# PCB_Plates_Combined_Eagle.net
KiCad netlist of a schematic drawn in EAGLE
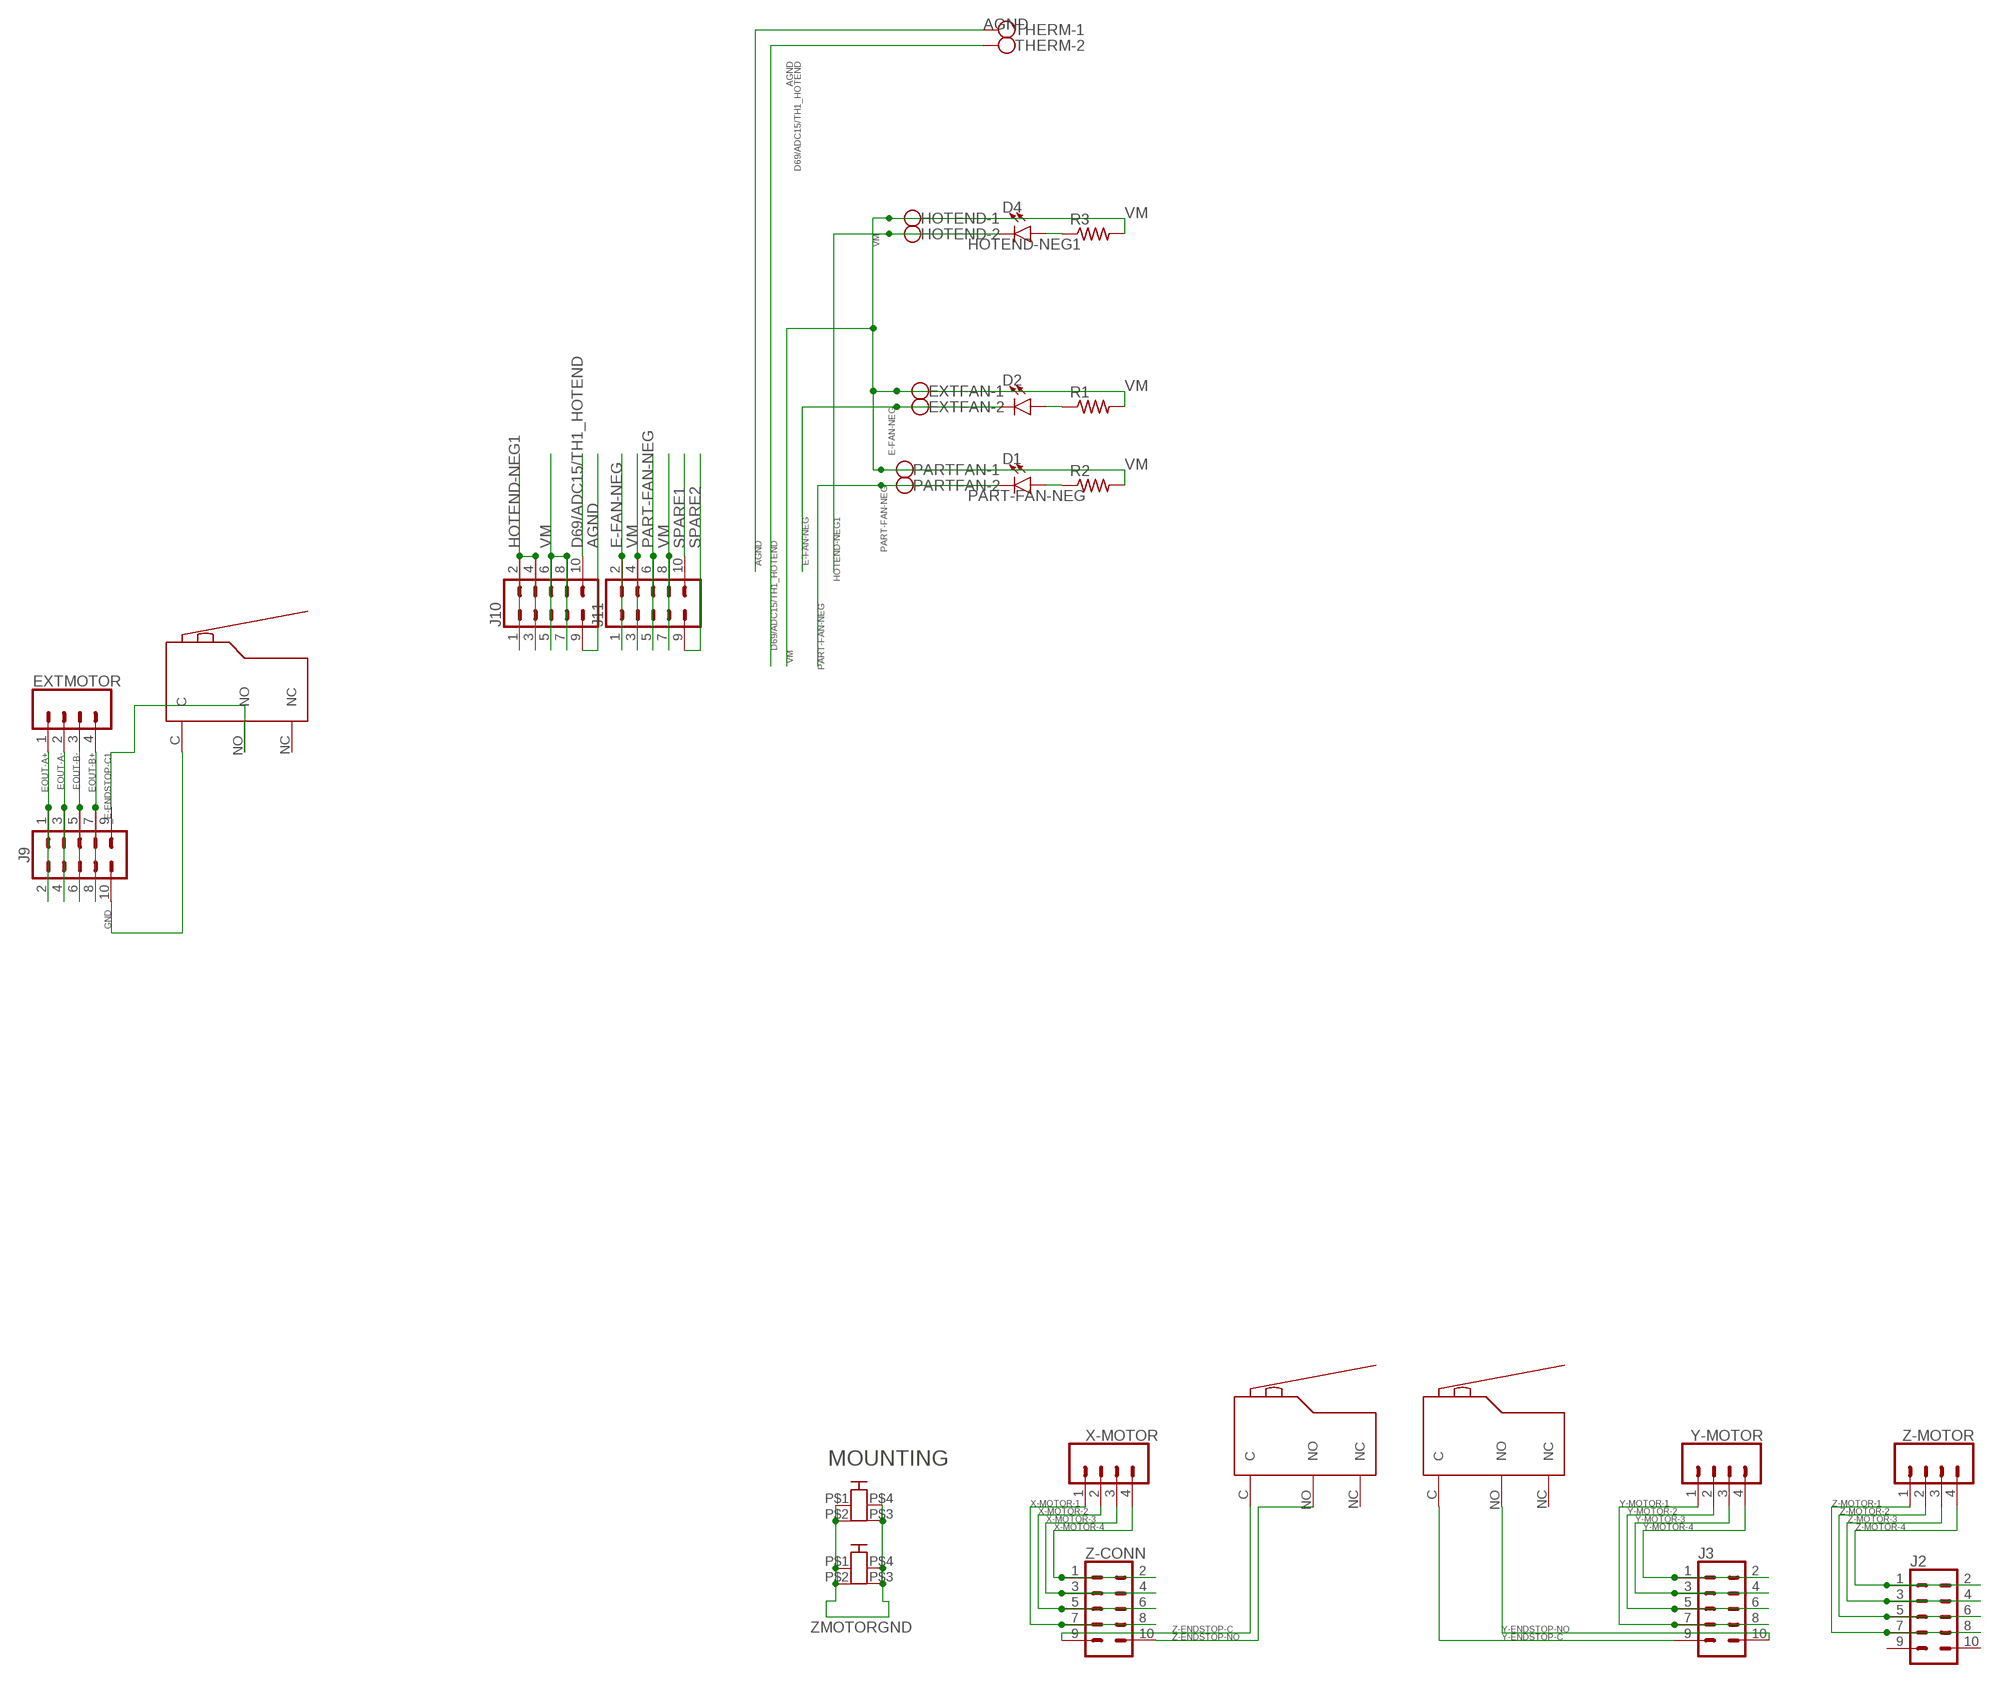
[diagram p0: schematic, sheet 1]

(export (version "E")
  (design (tool "Eeschema 10.0.6"))
  (components
    (comp (ref "CON1")
      (value "PCB-2M3")
      (footprint "eagle-import:PCB2-M3")
      (libsource (lib "eagle-import") (part "PCB-2M3"))
    )
    (comp (ref "CON7")
      (value "PCB-2M3")
      (footprint "eagle-import:PCB2-M3")
      (libsource (lib "eagle-import") (part "PCB-2M3"))
    )
    (comp (ref "D1")
      (value "LED-FKIT-1206")
      (footprint "eagle-import:FKIT-LED-1206")
      (libsource (lib "eagle-import") (part "LED-FKIT-1206"))
    )
    (comp (ref "D2")
      (value "LED-FKIT-1206")
      (footprint "eagle-import:FKIT-LED-1206")
      (libsource (lib "eagle-import") (part "LED-FKIT-1206"))
    )
    (comp (ref "D4")
      (value "LED-FKIT-1206")
      (footprint "eagle-import:FKIT-LED-1206")
      (libsource (lib "eagle-import") (part "LED-FKIT-1206"))
    )
    (comp (ref "EXTFAN")
      (value "W237-102")
      (footprint "eagle-import:W237-102")
      (fields (field (name "MPN") "237-102"))
      (libsource (lib "eagle-import") (part "W237-102"))
    )
    (comp (ref "EXTMOTOR")
      (value "CONN_04SCREW_LOCK")
      (footprint "eagle-import:SCREWTERMINAL-3.5MM-4_LOCK")
      (libsource (lib "eagle-import") (part "CONN_04SCREW_LOCK"))
    )
    (comp (ref "HOTEND")
      (value "W237-102")
      (footprint "eagle-import:W237-102")
      (fields (field (name "MPN") "237-102"))
      (libsource (lib "eagle-import") (part "W237-102"))
    )
    (comp (ref "J2")
      (value "CONN_05X2SHD_LOCK")
      (footprint "eagle-import:2X5-SHROUDED_LOCK")
      (libsource (lib "eagle-import") (part "CONN_05X2SHD_LOCK"))
    )
    (comp (ref "J3")
      (value "CONN_05X2SHD_LOCK")
      (footprint "eagle-import:2X5-SHROUDED_LOCK")
      (libsource (lib "eagle-import") (part "CONN_05X2SHD_LOCK"))
    )
    (comp (ref "J9")
      (value "CONN_05X2SHD_LOCK")
      (footprint "eagle-import:2X5-SHROUDED_LOCK")
      (libsource (lib "eagle-import") (part "CONN_05X2SHD_LOCK"))
    )
    (comp (ref "J10")
      (value "CONN_05X2SHD_LOCK")
      (footprint "eagle-import:2X5-SHROUDED_LOCK")
      (libsource (lib "eagle-import") (part "CONN_05X2SHD_LOCK"))
    )
    (comp (ref "J11")
      (value "CONN_05X2SHD_LOCK")
      (footprint "eagle-import:2X5-SHROUDED_LOCK")
      (libsource (lib "eagle-import") (part "CONN_05X2SHD_LOCK"))
    )
    (comp (ref "PARTFAN")
      (value "W237-102")
      (footprint "eagle-import:W237-102")
      (fields (field (name "MPN") "237-102"))
      (libsource (lib "eagle-import") (part "W237-102"))
    )
    (comp (ref "R1")
      (value "R-US_R1206")
      (footprint "eagle-import:R1206")
      (libsource (lib "eagle-import") (part "R-US_R1206"))
    )
    (comp (ref "R2")
      (value "R-US_R1206")
      (footprint "eagle-import:R1206")
      (libsource (lib "eagle-import") (part "R-US_R1206"))
    )
    (comp (ref "R3")
      (value "R-US_R1206")
      (footprint "eagle-import:R1206")
      (libsource (lib "eagle-import") (part "R-US_R1206"))
    )
    (comp (ref "THERM")
      (value "W237-102")
      (footprint "eagle-import:W237-102")
      (fields (field (name "MPN") "237-102"))
      (libsource (lib "eagle-import") (part "W237-102"))
    )
    (comp (ref "U$1")
      (value "Lever Microswitch Leftangle PCB mount, with Roller style lever, with a red roller")
      (footprint "eagle-import:LEVERMICROPCB-LEFTANGLE")
      (libsource (lib "eagle-import") (part "LEVERMICROPCBLEFTANGLE"))
    )
    (comp (ref "X-MOTOR")
      (value "CONN_04SCREW_LOCK")
      (footprint "eagle-import:SCREWTERMINAL-3.5MM-4_LOCK")
      (libsource (lib "eagle-import") (part "CONN_04SCREW_LOCK"))
    )
    (comp (ref "XENDSTOP")
      (value "Lever Microswitch Leftangle PCB mount, with Roller style lever, with a red roller")
      (footprint "eagle-import:LEVERMICROPCB-LEFTANGLE")
      (libsource (lib "eagle-import") (part "LEVERMICROPCBLEFTANGLE"))
    )
    (comp (ref "Y-MOTOR")
      (value "CONN_04SCREW_LOCK")
      (footprint "eagle-import:SCREWTERMINAL-3.5MM-4_LOCK")
      (libsource (lib "eagle-import") (part "CONN_04SCREW_LOCK"))
    )
    (comp (ref "Z-CONN")
      (value "CONN_05X2SHD_LOCK")
      (footprint "eagle-import:2X5-SHROUDED_LOCK")
      (libsource (lib "eagle-import") (part "CONN_05X2SHD_LOCK"))
    )
    (comp (ref "Z-MOTOR")
      (value "CONN_04SCREW_LOCK")
      (footprint "eagle-import:SCREWTERMINAL-3.5MM-4_LOCK")
      (libsource (lib "eagle-import") (part "CONN_04SCREW_LOCK"))
    )
    (comp (ref "ZENDSTOP")
      (value "Lever Microswitch Leftangle PCB mount, with Roller style lever, with a red roller")
      (footprint "eagle-import:LEVERMICROPCB-LEFTANGLE")
      (libsource (lib "eagle-import") (part "LEVERMICROPCBLEFTANGLE"))
    )
  )
  (nets
    (net (code "1") (name "/AGND") (class "Default")
      (node (ref "J10") (pin "9") (pinfunction "9_9") (pintype "passive"))
      (node (ref "THERM") (pin "1") (pinfunction "KL_1") (pintype "passive"))
    )
    (net (code "2") (name "/D69{slash}ADC15{slash}TH1_HOTEND") (class "Default")
      (node (ref "J10") (pin "10") (pinfunction "10_10") (pintype "passive"))
      (node (ref "THERM") (pin "2") (pinfunction "KL_2") (pintype "passive"))
    )
    (net (code "3") (name "/E-FAN-NEG") (class "Default")
      (node (ref "D2") (pin "C") (pinfunction "C_C") (pintype "passive"))
      (node (ref "EXTFAN") (pin "2") (pinfunction "KL_2") (pintype "passive"))
      (node (ref "J11") (pin "1") (pinfunction "1_1") (pintype "passive"))
      (node (ref "J11") (pin "2") (pinfunction "2_2") (pintype "passive"))
    )
    (net (code "4") (name "/EOUT-A+") (class "Default")
      (node (ref "EXTMOTOR") (pin "1") (pinfunction "1_1") (pintype "passive"))
      (node (ref "J9") (pin "1") (pinfunction "1_1") (pintype "passive"))
      (node (ref "J9") (pin "2") (pinfunction "2_2") (pintype "passive"))
    )
    (net (code "5") (name "/EOUT-A-") (class "Default")
      (node (ref "EXTMOTOR") (pin "2") (pinfunction "2_2") (pintype "passive"))
      (node (ref "J9") (pin "3") (pinfunction "3_3") (pintype "passive"))
      (node (ref "J9") (pin "4") (pinfunction "4_4") (pintype "passive"))
    )
    (net (code "6") (name "/EOUT-B+") (class "Default")
      (node (ref "EXTMOTOR") (pin "4") (pinfunction "4_4") (pintype "passive"))
      (node (ref "J9") (pin "7") (pinfunction "7_7") (pintype "passive"))
      (node (ref "J9") (pin "8") (pinfunction "8_8") (pintype "passive"))
    )
    (net (code "7") (name "/EOUT-B-") (class "Default")
      (node (ref "EXTMOTOR") (pin "3") (pinfunction "3_3") (pintype "passive"))
      (node (ref "J9") (pin "5") (pinfunction "5_5") (pintype "passive"))
      (node (ref "J9") (pin "6") (pinfunction "6_6") (pintype "passive"))
    )
    (net (code "8") (name "/GND") (class "Default")
      (node (ref "J9") (pin "10") (pinfunction "10_10") (pintype "passive"))
      (node (ref "XENDSTOP") (pin "C") (pinfunction "C_C") (pintype "bidirectional"))
    )
    (net (code "9") (name "/HOTEND-NEG1") (class "Default")
      (node (ref "D4") (pin "C") (pinfunction "C_C") (pintype "passive"))
      (node (ref "HOTEND") (pin "2") (pinfunction "KL_2") (pintype "passive"))
      (node (ref "J10") (pin "1") (pinfunction "1_1") (pintype "passive"))
      (node (ref "J10") (pin "2") (pinfunction "2_2") (pintype "passive"))
      (node (ref "J10") (pin "3") (pinfunction "3_3") (pintype "passive"))
      (node (ref "J10") (pin "4") (pinfunction "4_4") (pintype "passive"))
    )
    (net (code "10") (name "/PART-FAN-NEG") (class "Default")
      (node (ref "D1") (pin "C") (pinfunction "C_C") (pintype "passive"))
      (node (ref "J11") (pin "5") (pinfunction "5_5") (pintype "passive"))
      (node (ref "J11") (pin "6") (pinfunction "6_6") (pintype "passive"))
      (node (ref "PARTFAN") (pin "2") (pinfunction "KL_2") (pintype "passive"))
    )
    (net (code "11") (name "/SPARE1") (class "Default")
      (node (ref "J11") (pin "10") (pinfunction "10_10") (pintype "passive"))
    )
    (net (code "12") (name "/SPARE2") (class "Default")
      (node (ref "J11") (pin "9") (pinfunction "9_9") (pintype "passive"))
    )
    (net (code "13") (name "/VM") (class "Default")
      (node (ref "EXTFAN") (pin "1") (pinfunction "KL_1") (pintype "passive"))
      (node (ref "HOTEND") (pin "1") (pinfunction "KL_1") (pintype "passive"))
      (node (ref "J10") (pin "5") (pinfunction "5_5") (pintype "passive"))
      (node (ref "J10") (pin "6") (pinfunction "6_6") (pintype "passive"))
      (node (ref "J10") (pin "7") (pinfunction "7_7") (pintype "passive"))
      (node (ref "J10") (pin "8") (pinfunction "8_8") (pintype "passive"))
      (node (ref "J11") (pin "3") (pinfunction "3_3") (pintype "passive"))
      (node (ref "J11") (pin "4") (pinfunction "4_4") (pintype "passive"))
      (node (ref "J11") (pin "7") (pinfunction "7_7") (pintype "passive"))
      (node (ref "J11") (pin "8") (pinfunction "8_8") (pintype "passive"))
      (node (ref "PARTFAN") (pin "1") (pinfunction "KL_1") (pintype "passive"))
      (node (ref "R1") (pin "2") (pinfunction "2_2") (pintype "passive"))
      (node (ref "R2") (pin "2") (pinfunction "2_2") (pintype "passive"))
      (node (ref "R3") (pin "2") (pinfunction "2_2") (pintype "passive"))
    )
    (net (code "14") (name "/X-MOTOR-1") (class "Default")
      (node (ref "X-MOTOR") (pin "1") (pinfunction "1_1") (pintype "passive"))
      (node (ref "Z-CONN") (pin "7") (pinfunction "7_7") (pintype "passive"))
      (node (ref "Z-CONN") (pin "8") (pinfunction "8_8") (pintype "passive"))
    )
    (net (code "15") (name "/X-MOTOR-2") (class "Default")
      (node (ref "X-MOTOR") (pin "2") (pinfunction "2_2") (pintype "passive"))
      (node (ref "Z-CONN") (pin "5") (pinfunction "5_5") (pintype "passive"))
      (node (ref "Z-CONN") (pin "6") (pinfunction "6_6") (pintype "passive"))
    )
    (net (code "16") (name "/X-MOTOR-3") (class "Default")
      (node (ref "X-MOTOR") (pin "3") (pinfunction "3_3") (pintype "passive"))
      (node (ref "Z-CONN") (pin "3") (pinfunction "3_3") (pintype "passive"))
      (node (ref "Z-CONN") (pin "4") (pinfunction "4_4") (pintype "passive"))
    )
    (net (code "17") (name "/X-MOTOR-4") (class "Default")
      (node (ref "X-MOTOR") (pin "4") (pinfunction "4_4") (pintype "passive"))
      (node (ref "Z-CONN") (pin "1") (pinfunction "1_1") (pintype "passive"))
      (node (ref "Z-CONN") (pin "2") (pinfunction "2_2") (pintype "passive"))
    )
    (net (code "18") (name "/Y-ENDSTOP-C") (class "Default")
      (node (ref "J3") (pin "9") (pinfunction "9_9") (pintype "passive"))
      (node (ref "U$1") (pin "C") (pinfunction "C_C") (pintype "bidirectional"))
    )
    (net (code "19") (name "/Y-ENDSTOP-NO") (class "Default")
      (node (ref "J3") (pin "10") (pinfunction "10_10") (pintype "passive"))
      (node (ref "U$1") (pin "NO") (pinfunction "NO_NO") (pintype "bidirectional"))
    )
    (net (code "20") (name "/Y-MOTOR-1") (class "Default")
      (node (ref "J3") (pin "7") (pinfunction "7_7") (pintype "passive"))
      (node (ref "J3") (pin "8") (pinfunction "8_8") (pintype "passive"))
      (node (ref "Y-MOTOR") (pin "1") (pinfunction "1_1") (pintype "passive"))
    )
    (net (code "21") (name "/Y-MOTOR-2") (class "Default")
      (node (ref "J3") (pin "5") (pinfunction "5_5") (pintype "passive"))
      (node (ref "J3") (pin "6") (pinfunction "6_6") (pintype "passive"))
      (node (ref "Y-MOTOR") (pin "2") (pinfunction "2_2") (pintype "passive"))
    )
    (net (code "22") (name "/Y-MOTOR-3") (class "Default")
      (node (ref "J3") (pin "3") (pinfunction "3_3") (pintype "passive"))
      (node (ref "J3") (pin "4") (pinfunction "4_4") (pintype "passive"))
      (node (ref "Y-MOTOR") (pin "3") (pinfunction "3_3") (pintype "passive"))
    )
    (net (code "23") (name "/Y-MOTOR-4") (class "Default")
      (node (ref "J3") (pin "1") (pinfunction "1_1") (pintype "passive"))
      (node (ref "J3") (pin "2") (pinfunction "2_2") (pintype "passive"))
      (node (ref "Y-MOTOR") (pin "4") (pinfunction "4_4") (pintype "passive"))
    )
    (net (code "24") (name "/Z-ENDSTOP-C") (class "Default")
      (node (ref "Z-CONN") (pin "9") (pinfunction "9_9") (pintype "passive"))
      (node (ref "ZENDSTOP") (pin "C") (pinfunction "C_C") (pintype "bidirectional"))
    )
    (net (code "25") (name "/Z-ENDSTOP-NO") (class "Default")
      (node (ref "Z-CONN") (pin "10") (pinfunction "10_10") (pintype "passive"))
      (node (ref "ZENDSTOP") (pin "NO") (pinfunction "NO_NO") (pintype "bidirectional"))
    )
    (net (code "26") (name "/Z-MOTOR-1") (class "Default")
      (node (ref "J2") (pin "7") (pinfunction "7_7") (pintype "passive"))
      (node (ref "J2") (pin "8") (pinfunction "8_8") (pintype "passive"))
      (node (ref "Z-MOTOR") (pin "1") (pinfunction "1_1") (pintype "passive"))
    )
    (net (code "27") (name "/Z-MOTOR-2") (class "Default")
      (node (ref "J2") (pin "5") (pinfunction "5_5") (pintype "passive"))
      (node (ref "J2") (pin "6") (pinfunction "6_6") (pintype "passive"))
      (node (ref "Z-MOTOR") (pin "2") (pinfunction "2_2") (pintype "passive"))
    )
    (net (code "28") (name "/Z-MOTOR-3") (class "Default")
      (node (ref "J2") (pin "3") (pinfunction "3_3") (pintype "passive"))
      (node (ref "J2") (pin "4") (pinfunction "4_4") (pintype "passive"))
      (node (ref "Z-MOTOR") (pin "3") (pinfunction "3_3") (pintype "passive"))
    )
    (net (code "29") (name "/Z-MOTOR-4") (class "Default")
      (node (ref "J2") (pin "1") (pinfunction "1_1") (pintype "passive"))
      (node (ref "J2") (pin "2") (pinfunction "2_2") (pintype "passive"))
      (node (ref "Z-MOTOR") (pin "4") (pinfunction "4_4") (pintype "passive"))
    )
    (net (code "30") (name "/ZMOTORGND") (class "Default")
      (node (ref "CON1") (pin "P$1") (pinfunction "P$1_P$1") (pintype "bidirectional"))
      (node (ref "CON1") (pin "P$2") (pinfunction "P$2_P$2") (pintype "bidirectional"))
      (node (ref "CON1") (pin "P$3") (pinfunction "P$3_P$3") (pintype "bidirectional"))
      (node (ref "CON1") (pin "P$4") (pinfunction "P$4_P$4") (pintype "bidirectional"))
      (node (ref "CON7") (pin "P$1") (pinfunction "P$1_P$1") (pintype "bidirectional"))
      (node (ref "CON7") (pin "P$2") (pinfunction "P$2_P$2") (pintype "bidirectional"))
      (node (ref "CON7") (pin "P$3") (pinfunction "P$3_P$3") (pintype "bidirectional"))
      (node (ref "CON7") (pin "P$4") (pinfunction "P$4_P$4") (pintype "bidirectional"))
    )
    (net (code "31") (name "/_E-ENDSTOP-C1") (class "Default")
      (node (ref "J9") (pin "9") (pinfunction "9_9") (pintype "passive"))
      (node (ref "XENDSTOP") (pin "NO") (pinfunction "NO_NO") (pintype "bidirectional"))
    )
    (net (code "32") (name "Net-(D1-PadA)") (class "Default")
      (node (ref "D1") (pin "A") (pinfunction "A_A") (pintype "passive"))
      (node (ref "R2") (pin "1") (pinfunction "1_1") (pintype "passive"))
    )
    (net (code "33") (name "Net-(D2-PadA)") (class "Default")
      (node (ref "D2") (pin "A") (pinfunction "A_A") (pintype "passive"))
      (node (ref "R1") (pin "1") (pinfunction "1_1") (pintype "passive"))
    )
    (net (code "34") (name "Net-(D4-PadA)") (class "Default")
      (node (ref "D4") (pin "A") (pinfunction "A_A") (pintype "passive"))
      (node (ref "R3") (pin "1") (pinfunction "1_1") (pintype "passive"))
    )
    (net (code "35") (name "unconnected-(J2-Pad9)") (class "Default")
      (node (ref "J2") (pin "9") (pinfunction "9_9") (pintype "passive"))
    )
    (net (code "36") (name "unconnected-(J2-Pad10)") (class "Default")
      (node (ref "J2") (pin "10") (pinfunction "10_10") (pintype "passive"))
    )
    (net (code "37") (name "unconnected-(U$1-PadNC)") (class "Default")
      (node (ref "U$1") (pin "NC") (pinfunction "NC_NC") (pintype "bidirectional"))
    )
    (net (code "38") (name "unconnected-(XENDSTOP-PadNC)") (class "Default")
      (node (ref "XENDSTOP") (pin "NC") (pinfunction "NC_NC") (pintype "bidirectional"))
    )
    (net (code "39") (name "unconnected-(ZENDSTOP-PadNC)") (class "Default")
      (node (ref "ZENDSTOP") (pin "NC") (pinfunction "NC_NC") (pintype "bidirectional"))
    )
  )
)
